# Gral.net
KiCad netlist of a schematic drawn in Altium Designer
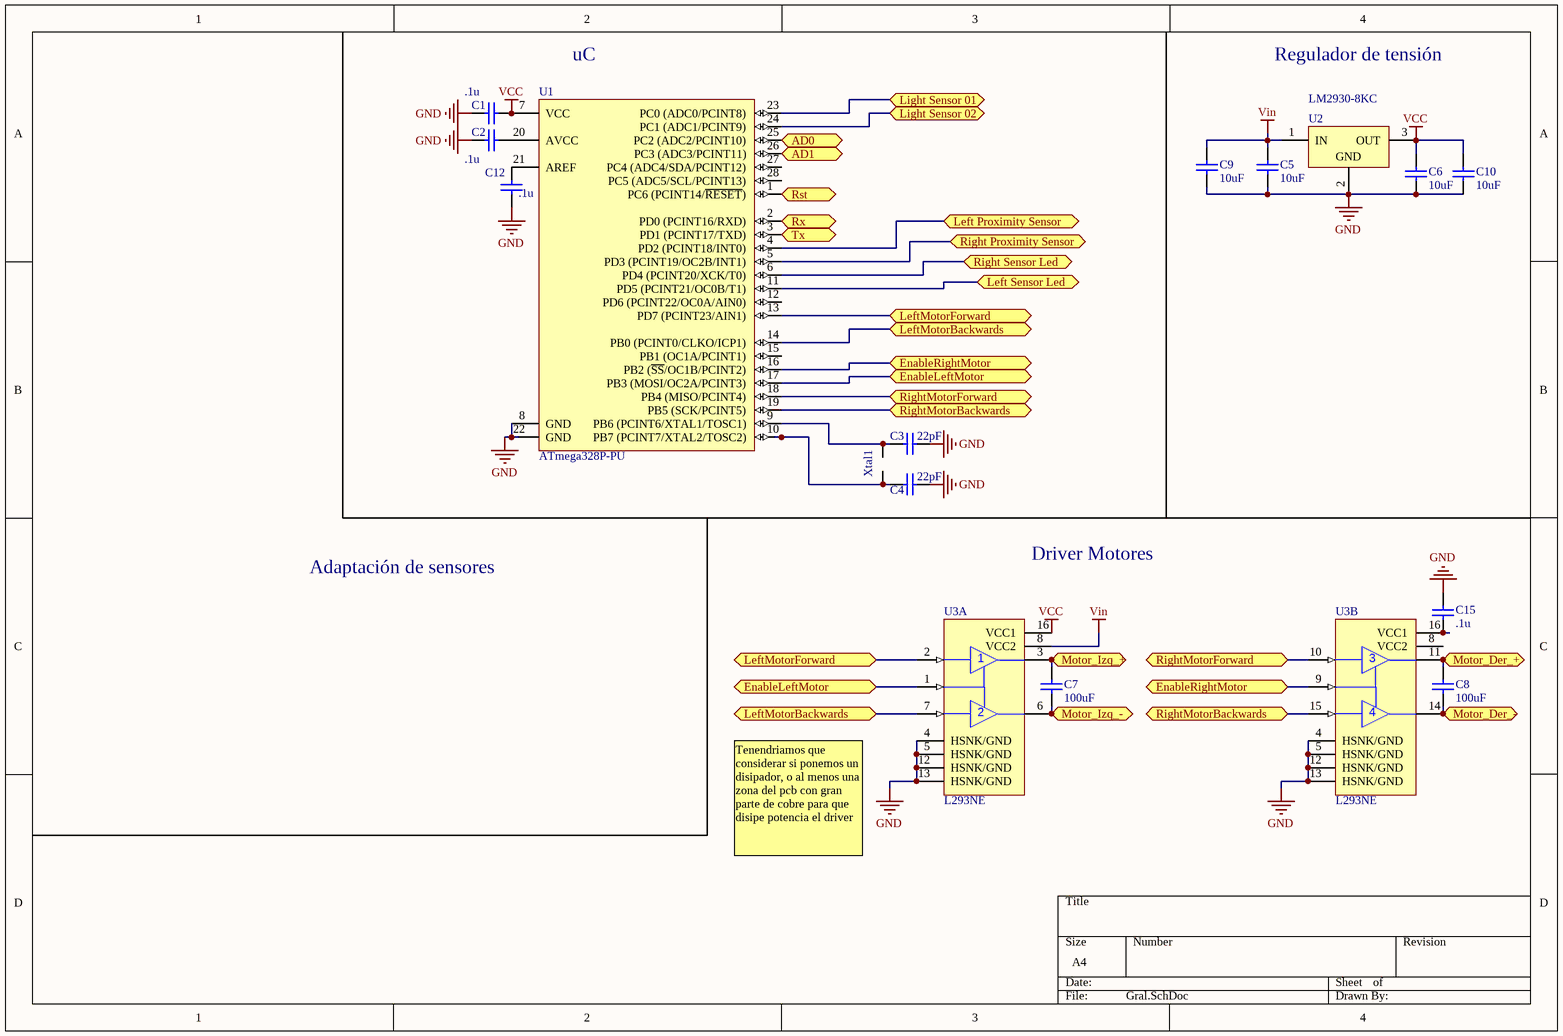
[diagram p0: Gral.SchDoc]

(export (version "E")
  (design (tool "Eeschema 10.0.6"))
  (components
    (comp (ref "C1")
      (value ".1u")
      (footprint "RAD-0.3")
      (description "Capacitor")
      (fields (field (name "Comment") "Cap") (field (name "PUBLISHER") "Altium Limited"))
      (libsource (lib "Miscellaneous Devices") (part "Cap"))
    )
    (comp (ref "C2")
      (value ".1u")
      (footprint "RAD-0.3")
      (description "Capacitor")
      (fields (field (name "Comment") "Cap") (field (name "PUBLISHER") "Altium Limited"))
      (libsource (lib "Miscellaneous Devices") (part "Cap"))
    )
    (comp (ref "C3")
      (value "22pF")
      (footprint "RAD-0.3")
      (description "Capacitor")
      (fields (field (name "Comment") "Cap") (field (name "PUBLISHER") "Altium Limited"))
      (libsource (lib "Miscellaneous Devices") (part "Cap"))
    )
    (comp (ref "C4")
      (value "22pF")
      (footprint "RAD-0.3")
      (description "Capacitor")
      (fields (field (name "Comment") "Cap") (field (name "PUBLISHER") "Altium Limited"))
      (libsource (lib "Miscellaneous Devices") (part "Cap"))
    )
    (comp (ref "C5")
      (value "10uF")
      (footprint "RAD-0.3")
      (description "Capacitor")
      (fields (field (name "Comment") "Cap") (field (name "PUBLISHER") "Altium Limited"))
      (libsource (lib "Miscellaneous Devices") (part "Cap"))
    )
    (comp (ref "C6")
      (value "10uF")
      (footprint "RAD-0.3")
      (description "Capacitor")
      (fields (field (name "Comment") "Cap") (field (name "PUBLISHER") "Altium Limited"))
      (libsource (lib "Miscellaneous Devices") (part "Cap"))
    )
    (comp (ref "C7")
      (value "100uF")
      (footprint "RAD-0.3")
      (description "Capacitor")
      (fields (field (name "Comment") "Cap") (field (name "PUBLISHER") "Altium Limited"))
      (libsource (lib "Miscellaneous Devices") (part "Cap"))
    )
    (comp (ref "C8")
      (value "100uF")
      (footprint "RAD-0.3")
      (description "Capacitor")
      (fields (field (name "Comment") "Cap") (field (name "PUBLISHER") "Altium Limited"))
      (libsource (lib "Miscellaneous Devices") (part "Cap"))
    )
    (comp (ref "C9")
      (value "10uF")
      (footprint "RAD-0.3")
      (description "Capacitor")
      (fields (field (name "Comment") "Cap") (field (name "PUBLISHER") "Altium Limited"))
      (libsource (lib "Miscellaneous Devices") (part "Cap"))
    )
    (comp (ref "C10")
      (value "10uF")
      (footprint "RAD-0.3")
      (description "Capacitor")
      (fields (field (name "Comment") "Cap") (field (name "PUBLISHER") "Altium Limited"))
      (libsource (lib "Miscellaneous Devices") (part "Cap"))
    )
    (comp (ref "C12")
      (value ".1u")
      (footprint "RAD-0.3")
      (description "Capacitor")
      (fields (field (name "Comment") "Cap") (field (name "PUBLISHER") "Altium Limited"))
      (libsource (lib "Miscellaneous Devices") (part "Cap"))
    )
    (comp (ref "C15")
      (value ".1u")
      (footprint "RAD-0.3")
      (description "Capacitor")
      (fields (field (name "Comment") "Cap") (field (name "PUBLISHER") "Altium Limited"))
      (libsource (lib "Miscellaneous Devices") (part "Cap"))
    )
    (comp (ref "U1")
      (value "ATmega328P-PU")
      (footprint "28P3")
      (fields (field (name "PUBLISHER") "Altium Limited"))
      (libsource (lib "Atmel Microcontroller 8-Bit megaAVR") (part "ATmega328P-PU"))
    )
    (comp (ref "U2")
      (value "LM2930-8KC")
      (footprint "KC03")
      (description "3-Terminal Positive Regulator")
      (fields (field (name "PUBLISHER") "Altium Limited"))
      (libsource (lib "TI Power Mgt Voltage Regulator") (part "LM2930-8KC"))
    )
    (comp (ref "U3")
      (value "L293NE")
      (footprint "NE016")
      (description "Quadruple Half-H Driver")
      (fields (field (name "PUBLISHER") "Altium Limited"))
      (libsource (lib "TI Interface Peripheral Driver") (part "L293NE"))
    )
    (comp (ref "Xtal1") (value "Xtal") (footprint "Xtal") (libsource (lib "Lib_pool") (part "Xtal")))
  )
  (nets
    (net (code "1") (name "/AD0") (class "Default")
      (node (ref "U1") (pin "25") (pinfunction "PC2_(ADC2/PCINT10)_25") (pintype "bidirectional"))
    )
    (net (code "2") (name "/AD1") (class "Default")
      (node (ref "U1") (pin "26") (pinfunction "PC3_(ADC3/PCINT11)_26") (pintype "bidirectional"))
    )
    (net (code "3") (name "/EnableLeftMotor") (class "Default")
      (node (ref "U1") (pin "17") (pinfunction "PB3_(MOSI/OC2A/PCINT3)_17") (pintype "bidirectional"))
      (node (ref "U3") (pin "1") (pinfunction "1,2EN_1") (pintype "input"))
    )
    (net (code "4") (name "/EnableRightMotor") (class "Default")
      (node (ref "U1") (pin "16") (pinfunction "PB2_(~{SS}/OC1B/PCINT2)_16") (pintype "bidirectional"))
      (node (ref "U3") (pin "9") (pinfunction "3,4EN_9") (pintype "input"))
    )
    (net (code "5") (name "/Left Proximity Sensor") (class "Default")
      (node (ref "U1") (pin "4") (pinfunction "PD2_(PCINT18/INT0)_4") (pintype "bidirectional"))
    )
    (net (code "6") (name "/Left Sensor Led") (class "Default")
      (node (ref "U1") (pin "11") (pinfunction "PD5_(PCINT21/OC0B/T1)_11") (pintype "bidirectional"))
    )
    (net (code "7") (name "/LeftMotorBackwards") (class "Default")
      (node (ref "U1") (pin "14") (pinfunction "PB0_(PCINT0/CLKO/ICP1)_14") (pintype "bidirectional"))
      (node (ref "U3") (pin "7") (pinfunction "2A_7") (pintype "input"))
    )
    (net (code "8") (name "/LeftMotorForward") (class "Default")
      (node (ref "U1") (pin "13") (pinfunction "PD7_(PCINT23/AIN1)_13") (pintype "bidirectional"))
      (node (ref "U3") (pin "2") (pinfunction "1A_2") (pintype "input"))
    )
    (net (code "9") (name "/Light Sensor 01") (class "Default")
      (node (ref "U1") (pin "23") (pinfunction "PC0_(ADC0/PCINT8)_23") (pintype "bidirectional"))
    )
    (net (code "10") (name "/Light Sensor 02") (class "Default")
      (node (ref "U1") (pin "24") (pinfunction "PC1_(ADC1/PCINT9)_24") (pintype "bidirectional"))
    )
    (net (code "11") (name "/Motor_Der_+") (class "Default")
      (node (ref "C8") (pin "2") (pinfunction "2_2") (pintype "passive"))
      (node (ref "U3") (pin "11") (pinfunction "3Y_11") (pintype "tri_state"))
    )
    (net (code "12") (name "/Motor_Der_-") (class "Default")
      (node (ref "C8") (pin "1") (pinfunction "1_1") (pintype "passive"))
      (node (ref "U3") (pin "14") (pinfunction "4Y_14") (pintype "tri_state"))
    )
    (net (code "13") (name "/Motor_Izq_+") (class "Default")
      (node (ref "C7") (pin "2") (pinfunction "2_2") (pintype "passive"))
      (node (ref "U3") (pin "3") (pinfunction "1Y_3") (pintype "tri_state"))
    )
    (net (code "14") (name "/Motor_Izq_-") (class "Default")
      (node (ref "C7") (pin "1") (pinfunction "1_1") (pintype "passive"))
      (node (ref "U3") (pin "6") (pinfunction "2Y_6") (pintype "tri_state"))
    )
    (net (code "15") (name "/Right Proximity Sensor") (class "Default")
      (node (ref "U1") (pin "5") (pinfunction "PD3_(PCINT19/OC2B/INT1)_5") (pintype "bidirectional"))
    )
    (net (code "16") (name "/Right Sensor Led") (class "Default")
      (node (ref "U1") (pin "6") (pinfunction "PD4_(PCINT20/XCK/T0)_6") (pintype "bidirectional"))
    )
    (net (code "17") (name "/RightMotorBackwards") (class "Default")
      (node (ref "U1") (pin "19") (pinfunction "PB5_(SCK/PCINT5)_19") (pintype "bidirectional"))
      (node (ref "U3") (pin "15") (pinfunction "4A_15") (pintype "input"))
    )
    (net (code "18") (name "/RightMotorForward") (class "Default")
      (node (ref "U1") (pin "18") (pinfunction "PB4_(MISO/PCINT4)_18") (pintype "bidirectional"))
      (node (ref "U3") (pin "10") (pinfunction "3A_10") (pintype "input"))
    )
    (net (code "19") (name "/Rst") (class "Default")
      (node (ref "U1") (pin "1") (pinfunction "PC6_(PCINT14/~{RESET})_1") (pintype "bidirectional"))
    )
    (net (code "20") (name "/Rx") (class "Default")
      (node (ref "U1") (pin "2") (pinfunction "PD0_(PCINT16/RXD)_2") (pintype "bidirectional"))
    )
    (net (code "21") (name "/Tx") (class "Default")
      (node (ref "U1") (pin "3") (pinfunction "PD1_(PCINT17/TXD)_3") (pintype "bidirectional"))
    )
    (net (code "22") (name "GND") (class "Default")
      (node (ref "C1") (pin "1") (pinfunction "1_1") (pintype "passive"))
      (node (ref "C10") (pin "1") (pinfunction "1_1") (pintype "passive"))
      (node (ref "C12") (pin "1") (pinfunction "1_1") (pintype "passive"))
      (node (ref "C15") (pin "1") (pinfunction "1_1") (pintype "passive"))
      (node (ref "C2") (pin "1") (pinfunction "1_1") (pintype "passive"))
      (node (ref "C3") (pin "2") (pinfunction "2_2") (pintype "passive"))
      (node (ref "C4") (pin "2") (pinfunction "2_2") (pintype "passive"))
      (node (ref "C5") (pin "1") (pinfunction "1_1") (pintype "passive"))
      (node (ref "C6") (pin "1") (pinfunction "1_1") (pintype "passive"))
      (node (ref "C9") (pin "1") (pinfunction "1_1") (pintype "passive"))
      (node (ref "U1") (pin "22") (pinfunction "GND_22") (pintype "power_in"))
      (node (ref "U1") (pin "8") (pinfunction "GND_8") (pintype "power_in"))
      (node (ref "U2") (pin "2") (pinfunction "GND_2") (pintype "power_in"))
      (node (ref "U3") (pin "12") (pinfunction "HSNK/GND_12") (pintype "power_in"))
      (node (ref "U3") (pin "13") (pinfunction "HSNK/GND_13") (pintype "power_in"))
      (node (ref "U3") (pin "4") (pinfunction "HSNK/GND_4") (pintype "power_in"))
      (node (ref "U3") (pin "5") (pinfunction "HSNK/GND_5") (pintype "power_in"))
    )
    (net (code "23") (name "Net-(U1-AREF)") (class "Default")
      (node (ref "C12") (pin "2") (pinfunction "2_2") (pintype "passive"))
      (node (ref "U1") (pin "21") (pinfunction "AREF_21") (pintype "power_in"))
    )
    (net (code "24") (name "Net-(U1-AVCC)") (class "Default")
      (node (ref "C2") (pin "2") (pinfunction "2_2") (pintype "passive"))
      (node (ref "U1") (pin "20") (pinfunction "AVCC_20") (pintype "power_in"))
    )
    (net (code "25") (name "Net-(U1-PB6_(PCINT6{slash}XTAL1{slash}TOSC1))") (class "Default")
      (node (ref "C3") (pin "1") (pinfunction "1_1") (pintype "passive"))
      (node (ref "U1") (pin "9") (pinfunction "PB6_(PCINT6/XTAL1/TOSC1)_9") (pintype "bidirectional"))
      (node (ref "Xtal1") (pin "2") (pinfunction "2_2") (pintype "passive"))
    )
    (net (code "26") (name "Net-(U1-PB7_(PCINT7{slash}XTAL2{slash}TOSC2))") (class "Default")
      (node (ref "C4") (pin "1") (pinfunction "1_1") (pintype "passive"))
      (node (ref "U1") (pin "10") (pinfunction "PB7_(PCINT7/XTAL2/TOSC2)_10") (pintype "bidirectional"))
      (node (ref "Xtal1") (pin "1") (pinfunction "1_1") (pintype "passive"))
    )
    (net (code "27") (name "Net-(U3B-VCC1)") (class "Default")
      (node (ref "C15") (pin "2") (pinfunction "2_2") (pintype "passive"))
      (node (ref "U3") (pin "16") (pinfunction "VCC1_16") (pintype "power_in"))
    )
    (net (code "28") (name "VCC") (class "Default")
      (node (ref "C1") (pin "2") (pinfunction "2_2") (pintype "passive"))
      (node (ref "C10") (pin "2") (pinfunction "2_2") (pintype "passive"))
      (node (ref "C6") (pin "2") (pinfunction "2_2") (pintype "passive"))
      (node (ref "U1") (pin "7") (pinfunction "VCC_7") (pintype "power_in"))
      (node (ref "U2") (pin "3") (pinfunction "OUT_3") (pintype "power_in"))
      (node (ref "U3") (pin "16") (pinfunction "VCC1_16") (pintype "power_in"))
    )
    (net (code "29") (name "Vin") (class "Default")
      (node (ref "C5") (pin "2") (pinfunction "2_2") (pintype "passive"))
      (node (ref "C9") (pin "2") (pinfunction "2_2") (pintype "passive"))
      (node (ref "U2") (pin "1") (pinfunction "IN_1") (pintype "power_in"))
      (node (ref "U3") (pin "8") (pinfunction "VCC2_8") (pintype "power_in"))
    )
    (net (code "30") (name "unconnected-(U1-PB1_(OC1A{slash}PCINT1)-Pad15)") (class "Default")
      (node (ref "U1") (pin "15") (pinfunction "PB1_(OC1A/PCINT1)_15") (pintype "bidirectional"))
    )
    (net (code "31") (name "unconnected-(U1-PC4_(ADC4{slash}SDA{slash}PCINT12)-Pad27)") (class "Default")
      (node (ref "U1") (pin "27") (pinfunction "PC4_(ADC4/SDA/PCINT12)_27") (pintype "bidirectional"))
    )
    (net (code "32") (name "unconnected-(U1-PC5_(ADC5{slash}SCL{slash}PCINT13)-Pad28)") (class "Default")
      (node (ref "U1") (pin "28") (pinfunction "PC5_(ADC5/SCL/PCINT13)_28") (pintype "bidirectional"))
    )
    (net (code "33") (name "unconnected-(U1-PD6_(PCINT22{slash}OC0A{slash}AIN0)-Pad12)") (class "Default")
      (node (ref "U1") (pin "12") (pinfunction "PD6_(PCINT22/OC0A/AIN0)_12") (pintype "bidirectional"))
    )
    (net (code "34") (name "unconnected-(U3B-VCC2-Pad8)") (class "Default")
      (node (ref "U3") (pin "8") (pinfunction "VCC2_8") (pintype "power_in"))
    )
  )
)
